# SCH_ACVoltageSensor_2025-03-02.net
KiCad netlist of a schematic drawn in EasyEDA
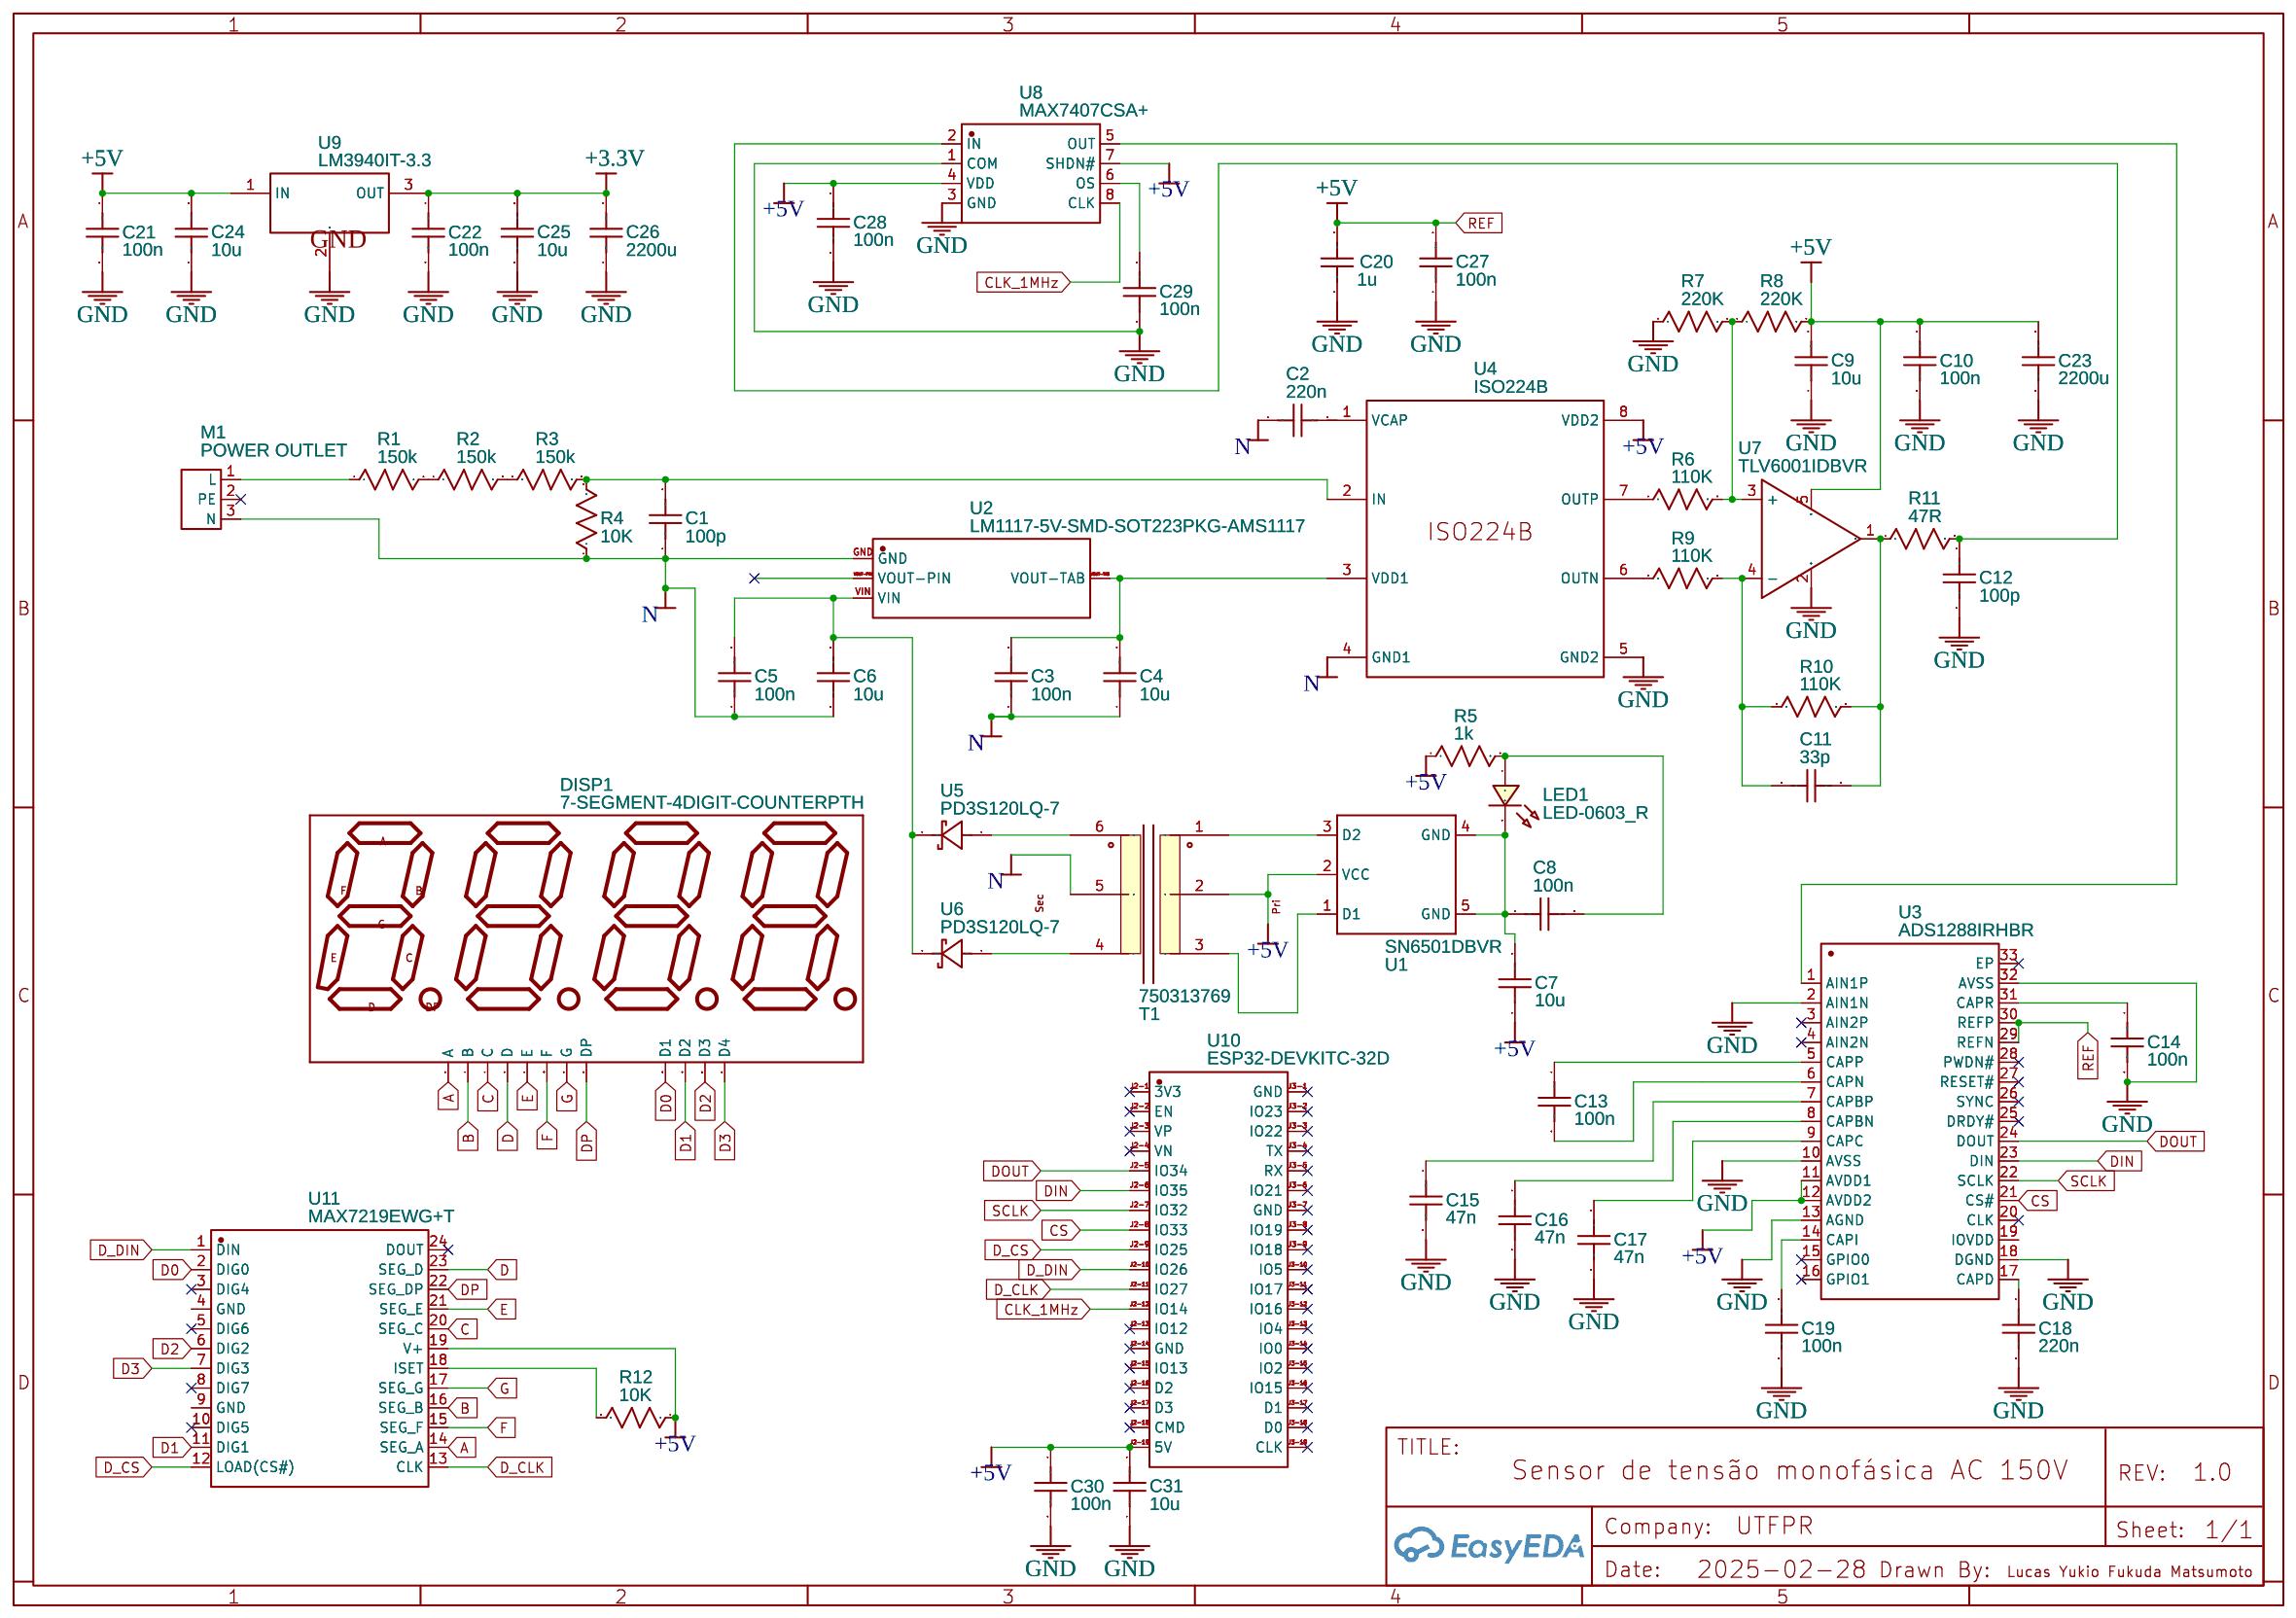
[diagram p0: schematic sheet]

(export (version "E")
  (design (tool "Eeschema 10.0.6"))
  (components
    (comp (ref "C1") (value "100p") (libsource (lib "") (part "C_0603_US_1")))
    (comp (ref "C2") (value "220n") (libsource (lib "") (part "C_0603_US_2")))
    (comp (ref "C3") (value "100n") (libsource (lib "") (part "C_0603_US_1")))
    (comp (ref "C4") (value "10u") (libsource (lib "") (part "C_0603_US_1")))
    (comp (ref "C5") (value "100n") (libsource (lib "") (part "C_0603_US_1")))
    (comp (ref "C6") (value "10u") (libsource (lib "") (part "C_0603_US_1")))
    (comp (ref "C7") (value "10u") (libsource (lib "") (part "C_0603_US_1")))
    (comp (ref "C8") (value "100n") (libsource (lib "") (part "C_0603_US_2")))
    (comp (ref "C9") (value "10u") (libsource (lib "") (part "C_0603_US_1")))
    (comp (ref "C10") (value "100n") (libsource (lib "") (part "C_0603_US")))
    (comp (ref "C11") (value "33p") (libsource (lib "") (part "C_0603_US_2")))
    (comp (ref "C12") (value "100p") (libsource (lib "") (part "C_0603_US_1")))
    (comp (ref "C13") (value "100n") (libsource (lib "") (part "C_0603_US")))
    (comp (ref "C14") (value "100n") (libsource (lib "") (part "C_0603_US")))
    (comp (ref "C15") (value "47n") (libsource (lib "") (part "C_0603_US")))
    (comp (ref "C16") (value "47n") (libsource (lib "") (part "C_0603_US")))
    (comp (ref "C17") (value "47n") (libsource (lib "") (part "C_0603_US")))
    (comp (ref "C18") (value "220n") (libsource (lib "") (part "C_0603_US")))
    (comp (ref "C19") (value "100n") (libsource (lib "") (part "C_0603_US")))
    (comp (ref "C20") (value "1u") (libsource (lib "") (part "C_0603_US_1")))
    (comp (ref "C21") (value "100n") (libsource (lib "") (part "C_0603_US")))
    (comp (ref "C22") (value "100n") (libsource (lib "") (part "C_0603_US")))
    (comp (ref "C23") (value "2200u") (libsource (lib "") (part "C_0603_US")))
    (comp (ref "C24") (value "10u") (libsource (lib "") (part "C_0603_US_1")))
    (comp (ref "C25") (value "10u") (libsource (lib "") (part "C_0603_US_1")))
    (comp (ref "C26") (value "2200u") (libsource (lib "") (part "C_0603_US_1")))
    (comp (ref "C27") (value "100n") (libsource (lib "") (part "C_0603_US_1")))
    (comp (ref "C28") (value "100n") (libsource (lib "") (part "C_0603_US")))
    (comp (ref "C29") (value "100n") (libsource (lib "") (part "C_0603_US")))
    (comp (ref "C30") (value "100n") (libsource (lib "") (part "C_0603_US")))
    (comp (ref "C31") (value "10u") (libsource (lib "") (part "C_0603_US_1")))
    (comp (ref "DISP1")
      (value "7-SEGMENT-4DIGIT-COUNTERPTH")
      (libsource (lib "") (part "7-SEGMENT-4DIGIT-COUNTERPTH"))
    )
    (comp (ref "LED1")
      (value "LED-0603_R")
      (fields
        (field (name "Manufacturer Part") "19-217/R6C-AL1M2VY/3T")
        (field (name "Manufacturer") "EVERLIGHT(台湾亿光)")
      )
      (libsource (lib "") (part "LED-0603_R"))
    )
    (comp (ref "M1") (value "POWER OUTLET") (libsource (lib "") (part "POWER OUTLET")))
    (comp (ref "R1") (value "150k") (libsource (lib "") (part "R_0603_US")))
    (comp (ref "R2") (value "150k") (libsource (lib "") (part "R_0603_US")))
    (comp (ref "R3") (value "150k") (libsource (lib "") (part "R_0603_US")))
    (comp (ref "R4") (value "10K") (libsource (lib "") (part "R_0603_US_2")))
    (comp (ref "R5") (value "1k") (libsource (lib "") (part "R_0603_US")))
    (comp (ref "R6") (value "110K") (libsource (lib "") (part "R_0603_US")))
    (comp (ref "R7") (value "220K") (libsource (lib "") (part "R_0603_US")))
    (comp (ref "R8") (value "220K") (libsource (lib "") (part "R_0603_US")))
    (comp (ref "R9") (value "110K") (libsource (lib "") (part "R_0603_US")))
    (comp (ref "R10") (value "110K") (libsource (lib "") (part "R_0603_US")))
    (comp (ref "R11") (value "47R") (libsource (lib "") (part "R_0603_US")))
    (comp (ref "R12") (value "10K") (libsource (lib "") (part "R_0603_US_1")))
    (comp (ref "T1") (value "750313769") (libsource (lib "") (part "750313769")))
    (comp (ref "U1")
      (value "SN6501DBVR")
      (fields (field (name "Manufacturer") "TI(德州仪器)"))
      (libsource (lib "") (part "SN6501DBVR"))
    )
    (comp (ref "U2")
      (value "LM1117-5V-SMD-SOT223PKG-AMS1117")
      (fields (field (name "Manufacturer Part") "AMS1117-3.3") (field (name "Manufacturer") "AMS"))
      (libsource (lib "") (part "LM1117-5V-SMD-SOT223PKG-AMS1117"))
    )
    (comp (ref "U3") (value "ADS1288IRHBR") (libsource (lib "") (part "ADS1288IRHBR")))
    (comp (ref "U4")
      (value "ISO224B")
      (fields (field (name "Manufacturer Part") "ISO224BDWVR") (field (name "Manufacturer") "TI"))
      (libsource (lib "") (part "ISO224B"))
    )
    (comp (ref "U5") (value "PD3S120LQ-7") (libsource (lib "") (part "PD3S120LQ-7")))
    (comp (ref "U6") (value "PD3S120LQ-7") (libsource (lib "") (part "PD3S120LQ-7")))
    (comp (ref "U7")
      (value "TLV6001IDBVR")
      (fields (field (name "Manufacturer") "TI"))
      (libsource (lib "") (part "TLV6001IDBVR"))
    )
    (comp (ref "U8")
      (value "MAX7407CSA+")
      (fields (field (name "Manufacturer") "ADI(亚德诺)/MAXIM(美信)"))
      (libsource (lib "") (part "MAX7407CSA+"))
    )
    (comp (ref "U9")
      (value "LM3940IT-3.3")
      (fields (field (name "Manufacturer") "TI(德州仪器)"))
      (libsource (lib "") (part "LM3940IT-3.3"))
    )
    (comp (ref "U10")
      (value "ESP32-DEVKITC-32D")
      (fields
        (field (name "Manufacturer Part") "ESP32-DevKitC-32D")
        (field (name "Manufacturer") "ESPRESSIF(乐鑫)")
      )
      (libsource (lib "") (part "ESP32-DEVKITC-32D"))
    )
    (comp (ref "U11")
      (value "MAX7219EWG+T")
      (fields (field (name "Manufacturer") "ADI(亚德诺)/MAXIM(美信)"))
      (libsource (lib "") (part "MAX7219EWG+T"))
    )
  )
  (nets
    (net (code "1") (name "+3.3V") (class "Default")
      (node (ref "C22") (pin "1") (pinfunction "1_1") (pintype "unspecified"))
      (node (ref "C25") (pin "2") (pinfunction "2_2") (pintype "unspecified"))
      (node (ref "C26") (pin "2") (pinfunction "2_2") (pintype "unspecified"))
      (node (ref "U9") (pin "3") (pinfunction "OUT_3") (pintype "passive"))
    )
    (net (code "2") (name "A") (class "Default")
      (node (ref "DISP1") (pin "11") (pinfunction "A_11") (pintype "unspecified"))
      (node (ref "U11") (pin "14") (pinfunction "SEG_A_14") (pintype "unspecified"))
    )
    (net (code "3") (name "B") (class "Default")
      (node (ref "DISP1") (pin "7") (pinfunction "B_7") (pintype "unspecified"))
      (node (ref "U11") (pin "16") (pinfunction "SEG_B_16") (pintype "unspecified"))
    )
    (net (code "4") (name "C") (class "Default")
      (node (ref "DISP1") (pin "4") (pinfunction "C_4") (pintype "unspecified"))
      (node (ref "U11") (pin "20") (pinfunction "SEG_C_20") (pintype "unspecified"))
    )
    (net (code "5") (name "CLK_1MHz") (class "Default")
      (node (ref "U10") (pin "J2-12") (pinfunction "IO14_J2-12") (pintype "unspecified"))
      (node (ref "U8") (pin "8") (pinfunction "CLK_8") (pintype "unspecified"))
    )
    (net (code "6") (name "CS") (class "Default")
      (node (ref "U10") (pin "J2-8") (pinfunction "IO33_J2-8") (pintype "unspecified"))
      (node (ref "U3") (pin "21") (pinfunction "CS#_21") (pintype "unspecified"))
    )
    (net (code "7") (name "D") (class "Default")
      (node (ref "DISP1") (pin "2") (pinfunction "D_2") (pintype "unspecified"))
      (node (ref "U11") (pin "23") (pinfunction "SEG_D_23") (pintype "unspecified"))
    )
    (net (code "8") (name "D0") (class "Default")
      (node (ref "DISP1") (pin "12") (pinfunction "D1_12") (pintype "unspecified"))
      (node (ref "U11") (pin "2") (pinfunction "DIG0_2") (pintype "unspecified"))
    )
    (net (code "9") (name "D1") (class "Default")
      (node (ref "DISP1") (pin "9") (pinfunction "D2_9") (pintype "unspecified"))
      (node (ref "U11") (pin "11") (pinfunction "DIG1_11") (pintype "unspecified"))
    )
    (net (code "10") (name "D2") (class "Default")
      (node (ref "DISP1") (pin "8") (pinfunction "D3_8") (pintype "unspecified"))
      (node (ref "U11") (pin "6") (pinfunction "DIG2_6") (pintype "unspecified"))
    )
    (net (code "11") (name "D3") (class "Default")
      (node (ref "DISP1") (pin "6") (pinfunction "D4_6") (pintype "unspecified"))
      (node (ref "U11") (pin "7") (pinfunction "DIG3_7") (pintype "unspecified"))
    )
    (net (code "12") (name "DIN") (class "Default")
      (node (ref "U10") (pin "J2-6") (pinfunction "IO35_J2-6") (pintype "unspecified"))
      (node (ref "U3") (pin "23") (pinfunction "DIN_23") (pintype "unspecified"))
    )
    (net (code "13") (name "DOUT") (class "Default")
      (node (ref "U10") (pin "J2-5") (pinfunction "IO34_J2-5") (pintype "unspecified"))
      (node (ref "U3") (pin "24") (pinfunction "DOUT_24") (pintype "unspecified"))
    )
    (net (code "14") (name "DP") (class "Default")
      (node (ref "DISP1") (pin "3") (pinfunction "DP_3") (pintype "unspecified"))
      (node (ref "U11") (pin "22") (pinfunction "SEG_DP_22") (pintype "unspecified"))
    )
    (net (code "15") (name "D_CLK") (class "Default")
      (node (ref "U10") (pin "J2-11") (pinfunction "IO27_J2-11") (pintype "unspecified"))
      (node (ref "U11") (pin "13") (pinfunction "CLK_13") (pintype "unspecified"))
    )
    (net (code "16") (name "D_CS") (class "Default")
      (node (ref "U10") (pin "J2-9") (pinfunction "IO25_J2-9") (pintype "unspecified"))
      (node (ref "U11") (pin "12") (pinfunction "LOAD(CS#)_12") (pintype "unspecified"))
    )
    (net (code "17") (name "D_DIN") (class "Default")
      (node (ref "U10") (pin "J2-10") (pinfunction "IO26_J2-10") (pintype "unspecified"))
      (node (ref "U11") (pin "1") (pinfunction "DIN_1") (pintype "unspecified"))
    )
    (net (code "18") (name "E") (class "Default")
      (node (ref "DISP1") (pin "1") (pinfunction "E_1") (pintype "unspecified"))
      (node (ref "U11") (pin "21") (pinfunction "SEG_E_21") (pintype "unspecified"))
    )
    (net (code "19") (name "F") (class "Default")
      (node (ref "DISP1") (pin "10") (pinfunction "F_10") (pintype "unspecified"))
      (node (ref "U11") (pin "15") (pinfunction "SEG_F_15") (pintype "unspecified"))
    )
    (net (code "20") (name "G") (class "Default")
      (node (ref "DISP1") (pin "5") (pinfunction "G_5") (pintype "unspecified"))
      (node (ref "U11") (pin "17") (pinfunction "SEG_G_17") (pintype "unspecified"))
    )
    (net (code "21") (name "GND") (class "Default")
      (node (ref "C10") (pin "2") (pinfunction "2_2") (pintype "unspecified"))
      (node (ref "C12") (pin "1") (pinfunction "1_1") (pintype "unspecified"))
      (node (ref "C14") (pin "2") (pinfunction "2_2") (pintype "unspecified"))
      (node (ref "C15") (pin "2") (pinfunction "2_2") (pintype "unspecified"))
      (node (ref "C16") (pin "2") (pinfunction "2_2") (pintype "unspecified"))
      (node (ref "C17") (pin "2") (pinfunction "2_2") (pintype "unspecified"))
      (node (ref "C18") (pin "2") (pinfunction "2_2") (pintype "unspecified"))
      (node (ref "C19") (pin "2") (pinfunction "2_2") (pintype "unspecified"))
      (node (ref "C20") (pin "1") (pinfunction "1_1") (pintype "unspecified"))
      (node (ref "C21") (pin "2") (pinfunction "2_2") (pintype "unspecified"))
      (node (ref "C22") (pin "2") (pinfunction "2_2") (pintype "unspecified"))
      (node (ref "C23") (pin "2") (pinfunction "2_2") (pintype "unspecified"))
      (node (ref "C24") (pin "1") (pinfunction "1_1") (pintype "unspecified"))
      (node (ref "C25") (pin "1") (pinfunction "1_1") (pintype "unspecified"))
      (node (ref "C26") (pin "1") (pinfunction "1_1") (pintype "unspecified"))
      (node (ref "C27") (pin "1") (pinfunction "1_1") (pintype "unspecified"))
      (node (ref "C28") (pin "2") (pinfunction "2_2") (pintype "unspecified"))
      (node (ref "C29") (pin "2") (pinfunction "2_2") (pintype "unspecified"))
      (node (ref "C30") (pin "2") (pinfunction "2_2") (pintype "unspecified"))
      (node (ref "C31") (pin "1") (pinfunction "1_1") (pintype "unspecified"))
      (node (ref "C9") (pin "1") (pinfunction "1_1") (pintype "unspecified"))
      (node (ref "R7") (pin "1") (pinfunction "1_1") (pintype "unspecified"))
      (node (ref "U3") (pin "10") (pinfunction "AVSS_10") (pintype "unspecified"))
      (node (ref "U3") (pin "13") (pinfunction "AGND_13") (pintype "unspecified"))
      (node (ref "U3") (pin "18") (pinfunction "DGND_18") (pintype "unspecified"))
      (node (ref "U3") (pin "2") (pinfunction "AIN1N_2") (pintype "unspecified"))
      (node (ref "U3") (pin "32") (pinfunction "AVSS_32") (pintype "unspecified"))
      (node (ref "U4") (pin "5") (pinfunction "GND2_5") (pintype "unspecified"))
      (node (ref "U7") (pin "2") (pinfunction "GND_2") (pintype "unspecified"))
      (node (ref "U8") (pin "1") (pinfunction "COM_1") (pintype "unspecified"))
      (node (ref "U8") (pin "3") (pinfunction "GND_3") (pintype "unspecified"))
      (node (ref "U9") (pin "2") (pinfunction "GND_2") (pintype "passive"))
    )
    (net (code "22") (name "N") (class "Default")
      (node (ref "C1") (pin "1") (pinfunction "1_1") (pintype "unspecified"))
      (node (ref "C2") (pin "1") (pinfunction "1_1") (pintype "unspecified"))
      (node (ref "C3") (pin "1") (pinfunction "1_1") (pintype "unspecified"))
      (node (ref "C4") (pin "1") (pinfunction "1_1") (pintype "unspecified"))
      (node (ref "C5") (pin "1") (pinfunction "1_1") (pintype "unspecified"))
      (node (ref "C6") (pin "1") (pinfunction "1_1") (pintype "unspecified"))
      (node (ref "M1") (pin "3") (pinfunction "N_3") (pintype "unspecified"))
      (node (ref "R4") (pin "1") (pinfunction "1_1") (pintype "unspecified"))
      (node (ref "T1") (pin "5") (pinfunction "5_5") (pintype "bidirectional"))
      (node (ref "U2") (pin "GND") (pinfunction "GND_GND") (pintype "unspecified"))
      (node (ref "U4") (pin "4") (pinfunction "GND1_4") (pintype "unspecified"))
    )
    (net (code "23") (name "Net-(C5-Pad2)") (class "Default")
      (node (ref "C5") (pin "2") (pinfunction "2_2") (pintype "unspecified"))
      (node (ref "C6") (pin "2") (pinfunction "2_2") (pintype "unspecified"))
      (node (ref "U2") (pin "VIN") (pinfunction "VIN_VIN") (pintype "unspecified"))
      (node (ref "U5") (pin "2") (pinfunction "2_2") (pintype "unspecified"))
      (node (ref "U6") (pin "2") (pinfunction "2_2") (pintype "unspecified"))
    )
    (net (code "24") (name "Net-(C7-Pad2)") (class "Default")
      (node (ref "C7") (pin "2") (pinfunction "2_2") (pintype "unspecified"))
      (node (ref "C8") (pin "1") (pinfunction "1_1") (pintype "unspecified"))
      (node (ref "LED1") (pin "2") (pinfunction "2_2") (pintype "unspecified"))
      (node (ref "U1") (pin "4") (pinfunction "GND_4") (pintype "unspecified"))
      (node (ref "U1") (pin "5") (pinfunction "GND_5") (pintype "unspecified"))
    )
    (net (code "25") (name "Net-(C8-Pad2)") (class "Default")
      (node (ref "C8") (pin "2") (pinfunction "2_2") (pintype "unspecified"))
      (node (ref "LED1") (pin "1") (pinfunction "1_1") (pintype "unspecified"))
      (node (ref "R5") (pin "2") (pinfunction "2_2") (pintype "unspecified"))
    )
    (net (code "26") (name "Net-(M1-L)") (class "Default")
      (node (ref "M1") (pin "1") (pinfunction "L_1") (pintype "unspecified"))
      (node (ref "R1") (pin "1") (pinfunction "1_1") (pintype "unspecified"))
    )
    (net (code "27") (name "Net-(R1-Pad2)") (class "Default")
      (node (ref "R1") (pin "2") (pinfunction "2_2") (pintype "unspecified"))
      (node (ref "R2") (pin "1") (pinfunction "1_1") (pintype "unspecified"))
    )
    (net (code "28") (name "Net-(R2-Pad2)") (class "Default")
      (node (ref "R2") (pin "2") (pinfunction "2_2") (pintype "unspecified"))
      (node (ref "R3") (pin "1") (pinfunction "1_1") (pintype "unspecified"))
    )
    (net (code "29") (name "Net-(T1-Pad4)") (class "Default")
      (node (ref "T1") (pin "4") (pinfunction "4_4") (pintype "bidirectional"))
      (node (ref "U6") (pin "1") (pinfunction "1_1") (pintype "unspecified"))
    )
    (net (code "30") (name "Net-(T1-Pad6)") (class "Default")
      (node (ref "T1") (pin "6") (pinfunction "6_6") (pintype "bidirectional"))
      (node (ref "U5") (pin "1") (pinfunction "1_1") (pintype "unspecified"))
    )
    (net (code "31") (name "Net-(U1-D1)") (class "Default")
      (node (ref "T1") (pin "3") (pinfunction "3_3") (pintype "bidirectional"))
      (node (ref "U1") (pin "1") (pinfunction "D1_1") (pintype "unspecified"))
    )
    (net (code "32") (name "Net-(U1-D2)") (class "Default")
      (node (ref "T1") (pin "1") (pinfunction "1_1") (pintype "bidirectional"))
      (node (ref "U1") (pin "3") (pinfunction "D2_3") (pintype "unspecified"))
    )
    (net (code "33") (name "Net-(U3-AIN1P)") (class "Default")
      (node (ref "U3") (pin "1") (pinfunction "AIN1P_1") (pintype "unspecified"))
      (node (ref "U8") (pin "5") (pinfunction "OUT_5") (pintype "unspecified"))
    )
    (net (code "34") (name "Net-(U3-CAPBN)") (class "Default")
      (node (ref "C16") (pin "1") (pinfunction "1_1") (pintype "unspecified"))
      (node (ref "U3") (pin "8") (pinfunction "CAPBN_8") (pintype "unspecified"))
    )
    (net (code "35") (name "Net-(U3-CAPBP)") (class "Default")
      (node (ref "C15") (pin "1") (pinfunction "1_1") (pintype "unspecified"))
      (node (ref "U3") (pin "7") (pinfunction "CAPBP_7") (pintype "unspecified"))
    )
    (net (code "36") (name "Net-(U3-CAPC)") (class "Default")
      (node (ref "C17") (pin "1") (pinfunction "1_1") (pintype "unspecified"))
      (node (ref "U3") (pin "9") (pinfunction "CAPC_9") (pintype "unspecified"))
    )
    (net (code "37") (name "Net-(U3-CAPD)") (class "Default")
      (node (ref "C18") (pin "1") (pinfunction "1_1") (pintype "unspecified"))
      (node (ref "U3") (pin "17") (pinfunction "CAPD_17") (pintype "unspecified"))
    )
    (net (code "38") (name "Net-(U3-CAPI)") (class "Default")
      (node (ref "C19") (pin "1") (pinfunction "1_1") (pintype "unspecified"))
      (node (ref "U3") (pin "14") (pinfunction "CAPI_14") (pintype "unspecified"))
    )
    (net (code "39") (name "Net-(U3-CAPN)") (class "Default")
      (node (ref "C13") (pin "2") (pinfunction "2_2") (pintype "unspecified"))
      (node (ref "U3") (pin "6") (pinfunction "CAPN_6") (pintype "unspecified"))
    )
    (net (code "40") (name "Net-(U3-CAPP)") (class "Default")
      (node (ref "C13") (pin "1") (pinfunction "1_1") (pintype "unspecified"))
      (node (ref "U3") (pin "5") (pinfunction "CAPP_5") (pintype "unspecified"))
    )
    (net (code "41") (name "Net-(U3-CAPR)") (class "Default")
      (node (ref "C14") (pin "1") (pinfunction "1_1") (pintype "unspecified"))
      (node (ref "U3") (pin "31") (pinfunction "CAPR_31") (pintype "unspecified"))
    )
    (net (code "42") (name "Net-(U4-IN)") (class "Default")
      (node (ref "C1") (pin "2") (pinfunction "2_2") (pintype "unspecified"))
      (node (ref "R3") (pin "2") (pinfunction "2_2") (pintype "unspecified"))
      (node (ref "R4") (pin "2") (pinfunction "2_2") (pintype "unspecified"))
      (node (ref "U4") (pin "2") (pinfunction "IN_2") (pintype "unspecified"))
    )
    (net (code "43") (name "Net-(U4-OUTN)") (class "Default")
      (node (ref "R9") (pin "1") (pinfunction "1_1") (pintype "unspecified"))
      (node (ref "U4") (pin "6") (pinfunction "OUTN_6") (pintype "unspecified"))
    )
    (net (code "44") (name "Net-(U4-OUTP)") (class "Default")
      (node (ref "R6") (pin "1") (pinfunction "1_1") (pintype "unspecified"))
      (node (ref "U4") (pin "7") (pinfunction "OUTP_7") (pintype "unspecified"))
    )
    (net (code "45") (name "Net-(U4-VDD1)") (class "Default")
      (node (ref "C3") (pin "2") (pinfunction "2_2") (pintype "unspecified"))
      (node (ref "C4") (pin "2") (pinfunction "2_2") (pintype "unspecified"))
      (node (ref "U2") (pin "VOUT-TAB") (pinfunction "VOUT-TAB_VOUT-TAB") (pintype "unspecified"))
      (node (ref "U4") (pin "3") (pinfunction "VDD1_3") (pintype "unspecified"))
    )
    (net (code "46") (name "Net-(U7-+)") (class "Default")
      (node (ref "R6") (pin "2") (pinfunction "2_2") (pintype "unspecified"))
      (node (ref "R7") (pin "2") (pinfunction "2_2") (pintype "unspecified"))
      (node (ref "R8") (pin "1") (pinfunction "1_1") (pintype "unspecified"))
      (node (ref "U7") (pin "3") (pinfunction "+_3") (pintype "unspecified"))
    )
    (net (code "47") (name "Net-(U7--)") (class "Default")
      (node (ref "C11") (pin "1") (pinfunction "1_1") (pintype "unspecified"))
      (node (ref "R10") (pin "1") (pinfunction "1_1") (pintype "unspecified"))
      (node (ref "R9") (pin "2") (pinfunction "2_2") (pintype "unspecified"))
      (node (ref "U7") (pin "4") (pinfunction "-_4") (pintype "unspecified"))
    )
    (net (code "48") (name "Net-(U7-OUT)") (class "Default")
      (node (ref "C11") (pin "2") (pinfunction "2_2") (pintype "unspecified"))
      (node (ref "R10") (pin "2") (pinfunction "2_2") (pintype "unspecified"))
      (node (ref "R11") (pin "1") (pinfunction "1_1") (pintype "unspecified"))
      (node (ref "U7") (pin "1") (pinfunction "OUT_1") (pintype "unspecified"))
    )
    (net (code "49") (name "Net-(U8-IN)") (class "Default")
      (node (ref "C12") (pin "2") (pinfunction "2_2") (pintype "unspecified"))
      (node (ref "R11") (pin "2") (pinfunction "2_2") (pintype "unspecified"))
      (node (ref "U8") (pin "2") (pinfunction "IN_2") (pintype "unspecified"))
    )
    (net (code "50") (name "Net-(U8-OS)") (class "Default")
      (node (ref "C29") (pin "1") (pinfunction "1_1") (pintype "unspecified"))
      (node (ref "U8") (pin "6") (pinfunction "OS_6") (pintype "unspecified"))
    )
    (net (code "51") (name "Net-(U11-ISET)") (class "Default")
      (node (ref "R12") (pin "2") (pinfunction "2_2") (pintype "unspecified"))
      (node (ref "U11") (pin "18") (pinfunction "ISET_18") (pintype "unspecified"))
    )
    (net (code "52") (name "REF") (class "Default")
      (node (ref "C10") (pin "1") (pinfunction "1_1") (pintype "unspecified"))
      (node (ref "C20") (pin "2") (pinfunction "2_2") (pintype "unspecified"))
      (node (ref "C21") (pin "1") (pinfunction "1_1") (pintype "unspecified"))
      (node (ref "C23") (pin "1") (pinfunction "1_1") (pintype "unspecified"))
      (node (ref "C24") (pin "2") (pinfunction "2_2") (pintype "unspecified"))
      (node (ref "C27") (pin "2") (pinfunction "2_2") (pintype "unspecified"))
      (node (ref "C28") (pin "1") (pinfunction "1_1") (pintype "unspecified"))
      (node (ref "C30") (pin "1") (pinfunction "1_1") (pintype "unspecified"))
      (node (ref "C31") (pin "2") (pinfunction "2_2") (pintype "unspecified"))
      (node (ref "C7") (pin "1") (pinfunction "1_1") (pintype "unspecified"))
      (node (ref "C9") (pin "2") (pinfunction "2_2") (pintype "unspecified"))
      (node (ref "R12") (pin "1") (pinfunction "1_1") (pintype "unspecified"))
      (node (ref "R5") (pin "1") (pinfunction "1_1") (pintype "unspecified"))
      (node (ref "R8") (pin "2") (pinfunction "2_2") (pintype "unspecified"))
      (node (ref "T1") (pin "2") (pinfunction "2_2") (pintype "bidirectional"))
      (node (ref "U1") (pin "2") (pinfunction "VCC_2") (pintype "unspecified"))
      (node (ref "U10") (pin "J2-19") (pinfunction "5V_J2-19") (pintype "unspecified"))
      (node (ref "U11") (pin "19") (pinfunction "V+_19") (pintype "unspecified"))
      (node (ref "U3") (pin "11") (pinfunction "AVDD1_11") (pintype "unspecified"))
      (node (ref "U3") (pin "12") (pinfunction "AVDD2_12") (pintype "unspecified"))
      (node (ref "U3") (pin "29") (pinfunction "REFN_29") (pintype "unspecified"))
      (node (ref "U3") (pin "30") (pinfunction "REFP_30") (pintype "unspecified"))
      (node (ref "U4") (pin "8") (pinfunction "VDD2_8") (pintype "unspecified"))
      (node (ref "U7") (pin "5") (pinfunction "VDD_5") (pintype "unspecified"))
      (node (ref "U8") (pin "4") (pinfunction "VDD_4") (pintype "unspecified"))
      (node (ref "U8") (pin "7") (pinfunction "SHDN#_7") (pintype "unspecified"))
      (node (ref "U9") (pin "1") (pinfunction "IN_1") (pintype "passive"))
    )
    (net (code "53") (name "SCLK") (class "Default")
      (node (ref "U10") (pin "J2-7") (pinfunction "IO32_J2-7") (pintype "unspecified"))
      (node (ref "U3") (pin "22") (pinfunction "SCLK_22") (pintype "unspecified"))
    )
    (net (code "54") (name "unconnected-(C2-Pad2)") (class "Default")
      (node (ref "C2") (pin "2") (pinfunction "2_2") (pintype "unspecified"))
    )
    (net (code "55") (name "unconnected-(M1-PE-Pad2)") (class "Default")
      (node (ref "M1") (pin "2") (pinfunction "PE_2") (pintype "unspecified+no_connect"))
    )
    (net (code "56") (name "unconnected-(U2-PadVOUT-PIN)") (class "Default")
      (node (ref "U2") (pin "VOUT-PIN") (pinfunction "VOUT-PIN_VOUT-PIN") (pintype "unspecified+no_connect"))
    )
    (net (code "57") (name "unconnected-(U3-AIN2N-Pad4)") (class "Default")
      (node (ref "U3") (pin "4") (pinfunction "AIN2N_4") (pintype "unspecified+no_connect"))
    )
    (net (code "58") (name "unconnected-(U3-AIN2P-Pad3)") (class "Default")
      (node (ref "U3") (pin "3") (pinfunction "AIN2P_3") (pintype "unspecified+no_connect"))
    )
    (net (code "59") (name "unconnected-(U3-CLK-Pad20)") (class "Default")
      (node (ref "U3") (pin "20") (pinfunction "CLK_20") (pintype "unspecified+no_connect"))
    )
    (net (code "60") (name "unconnected-(U3-DRDY#-Pad25)") (class "Default")
      (node (ref "U3") (pin "25") (pinfunction "DRDY#_25") (pintype "unspecified+no_connect"))
    )
    (net (code "61") (name "unconnected-(U3-EP-Pad33)") (class "Default")
      (node (ref "U3") (pin "33") (pinfunction "EP_33") (pintype "unspecified+no_connect"))
    )
    (net (code "62") (name "unconnected-(U3-GPIO0-Pad15)") (class "Default")
      (node (ref "U3") (pin "15") (pinfunction "GPIO0_15") (pintype "unspecified+no_connect"))
    )
    (net (code "63") (name "unconnected-(U3-GPIO1-Pad16)") (class "Default")
      (node (ref "U3") (pin "16") (pinfunction "GPIO1_16") (pintype "unspecified+no_connect"))
    )
    (net (code "64") (name "unconnected-(U3-IOVDD-Pad19)") (class "Default")
      (node (ref "U3") (pin "19") (pinfunction "IOVDD_19") (pintype "unspecified"))
    )
    (net (code "65") (name "unconnected-(U3-PWDN#-Pad28)") (class "Default")
      (node (ref "U3") (pin "28") (pinfunction "PWDN#_28") (pintype "unspecified+no_connect"))
    )
    (net (code "66") (name "unconnected-(U3-RESET#-Pad27)") (class "Default")
      (node (ref "U3") (pin "27") (pinfunction "RESET#_27") (pintype "unspecified+no_connect"))
    )
    (net (code "67") (name "unconnected-(U3-SYNC-Pad26)") (class "Default")
      (node (ref "U3") (pin "26") (pinfunction "SYNC_26") (pintype "unspecified+no_connect"))
    )
    (net (code "68") (name "unconnected-(U4-VCAP-Pad1)") (class "Default")
      (node (ref "U4") (pin "1") (pinfunction "VCAP_1") (pintype "unspecified"))
    )
    (net (code "69") (name "unconnected-(U10-3V3-PadJ2-1)") (class "Default")
      (node (ref "U10") (pin "J2-1") (pinfunction "3V3_J2-1") (pintype "unspecified+no_connect"))
    )
    (net (code "70") (name "unconnected-(U10-CLK-PadJ3-19)") (class "Default")
      (node (ref "U10") (pin "J3-19") (pinfunction "CLK_J3-19") (pintype "unspecified+no_connect"))
    )
    (net (code "71") (name "unconnected-(U10-CMD-PadJ2-18)") (class "Default")
      (node (ref "U10") (pin "J2-18") (pinfunction "CMD_J2-18") (pintype "unspecified+no_connect"))
    )
    (net (code "72") (name "unconnected-(U10-D0-PadJ3-18)") (class "Default")
      (node (ref "U10") (pin "J3-18") (pinfunction "D0_J3-18") (pintype "unspecified+no_connect"))
    )
    (net (code "73") (name "unconnected-(U10-D1-PadJ3-17)") (class "Default")
      (node (ref "U10") (pin "J3-17") (pinfunction "D1_J3-17") (pintype "unspecified+no_connect"))
    )
    (net (code "74") (name "unconnected-(U10-D2-PadJ2-16)") (class "Default")
      (node (ref "U10") (pin "J2-16") (pinfunction "D2_J2-16") (pintype "unspecified+no_connect"))
    )
    (net (code "75") (name "unconnected-(U10-D3-PadJ2-17)") (class "Default")
      (node (ref "U10") (pin "J2-17") (pinfunction "D3_J2-17") (pintype "unspecified+no_connect"))
    )
    (net (code "76") (name "unconnected-(U10-EN-PadJ2-2)") (class "Default")
      (node (ref "U10") (pin "J2-2") (pinfunction "EN_J2-2") (pintype "unspecified+no_connect"))
    )
    (net (code "77") (name "unconnected-(U10-GND-PadJ2-14)") (class "Default")
      (node (ref "U10") (pin "J2-14") (pinfunction "GND_J2-14") (pintype "unspecified+no_connect"))
    )
    (net (code "78") (name "unconnected-(U10-GND-PadJ3-1)") (class "Default")
      (node (ref "U10") (pin "J3-1") (pinfunction "GND_J3-1") (pintype "unspecified+no_connect"))
    )
    (net (code "79") (name "unconnected-(U10-GND-PadJ3-7)") (class "Default")
      (node (ref "U10") (pin "J3-7") (pinfunction "GND_J3-7") (pintype "unspecified+no_connect"))
    )
    (net (code "80") (name "unconnected-(U10-IO0-PadJ3-14)") (class "Default")
      (node (ref "U10") (pin "J3-14") (pinfunction "IO0_J3-14") (pintype "unspecified+no_connect"))
    )
    (net (code "81") (name "unconnected-(U10-IO2-PadJ3-15)") (class "Default")
      (node (ref "U10") (pin "J3-15") (pinfunction "IO2_J3-15") (pintype "unspecified+no_connect"))
    )
    (net (code "82") (name "unconnected-(U10-IO4-PadJ3-13)") (class "Default")
      (node (ref "U10") (pin "J3-13") (pinfunction "IO4_J3-13") (pintype "unspecified+no_connect"))
    )
    (net (code "83") (name "unconnected-(U10-IO5-PadJ3-10)") (class "Default")
      (node (ref "U10") (pin "J3-10") (pinfunction "IO5_J3-10") (pintype "unspecified+no_connect"))
    )
    (net (code "84") (name "unconnected-(U10-IO12-PadJ2-13)") (class "Default")
      (node (ref "U10") (pin "J2-13") (pinfunction "IO12_J2-13") (pintype "unspecified+no_connect"))
    )
    (net (code "85") (name "unconnected-(U10-IO13-PadJ2-15)") (class "Default")
      (node (ref "U10") (pin "J2-15") (pinfunction "IO13_J2-15") (pintype "unspecified+no_connect"))
    )
    (net (code "86") (name "unconnected-(U10-IO15-PadJ3-16)") (class "Default")
      (node (ref "U10") (pin "J3-16") (pinfunction "IO15_J3-16") (pintype "unspecified+no_connect"))
    )
    (net (code "87") (name "unconnected-(U10-IO16-PadJ3-12)") (class "Default")
      (node (ref "U10") (pin "J3-12") (pinfunction "IO16_J3-12") (pintype "unspecified+no_connect"))
    )
    (net (code "88") (name "unconnected-(U10-IO17-PadJ3-11)") (class "Default")
      (node (ref "U10") (pin "J3-11") (pinfunction "IO17_J3-11") (pintype "unspecified+no_connect"))
    )
    (net (code "89") (name "unconnected-(U10-IO18-PadJ3-9)") (class "Default")
      (node (ref "U10") (pin "J3-9") (pinfunction "IO18_J3-9") (pintype "unspecified+no_connect"))
    )
    (net (code "90") (name "unconnected-(U10-IO19-PadJ3-8)") (class "Default")
      (node (ref "U10") (pin "J3-8") (pinfunction "IO19_J3-8") (pintype "unspecified+no_connect"))
    )
    (net (code "91") (name "unconnected-(U10-IO21-PadJ3-6)") (class "Default")
      (node (ref "U10") (pin "J3-6") (pinfunction "IO21_J3-6") (pintype "unspecified+no_connect"))
    )
    (net (code "92") (name "unconnected-(U10-IO22-PadJ3-3)") (class "Default")
      (node (ref "U10") (pin "J3-3") (pinfunction "IO22_J3-3") (pintype "unspecified+no_connect"))
    )
    (net (code "93") (name "unconnected-(U10-IO23-PadJ3-2)") (class "Default")
      (node (ref "U10") (pin "J3-2") (pinfunction "IO23_J3-2") (pintype "unspecified+no_connect"))
    )
    (net (code "94") (name "unconnected-(U10-RX-PadJ3-5)") (class "Default")
      (node (ref "U10") (pin "J3-5") (pinfunction "RX_J3-5") (pintype "unspecified+no_connect"))
    )
    (net (code "95") (name "unconnected-(U10-TX-PadJ3-4)") (class "Default")
      (node (ref "U10") (pin "J3-4") (pinfunction "TX_J3-4") (pintype "unspecified+no_connect"))
    )
    (net (code "96") (name "unconnected-(U10-VN-PadJ2-4)") (class "Default")
      (node (ref "U10") (pin "J2-4") (pinfunction "VN_J2-4") (pintype "unspecified+no_connect"))
    )
    (net (code "97") (name "unconnected-(U10-VP-PadJ2-3)") (class "Default")
      (node (ref "U10") (pin "J2-3") (pinfunction "VP_J2-3") (pintype "unspecified+no_connect"))
    )
    (net (code "98") (name "unconnected-(U11-DIG4-Pad3)") (class "Default")
      (node (ref "U11") (pin "3") (pinfunction "DIG4_3") (pintype "unspecified+no_connect"))
    )
    (net (code "99") (name "unconnected-(U11-DIG5-Pad10)") (class "Default")
      (node (ref "U11") (pin "10") (pinfunction "DIG5_10") (pintype "unspecified+no_connect"))
    )
    (net (code "100") (name "unconnected-(U11-DIG6-Pad5)") (class "Default")
      (node (ref "U11") (pin "5") (pinfunction "DIG6_5") (pintype "unspecified+no_connect"))
    )
    (net (code "101") (name "unconnected-(U11-DIG7-Pad8)") (class "Default")
      (node (ref "U11") (pin "8") (pinfunction "DIG7_8") (pintype "unspecified+no_connect"))
    )
    (net (code "102") (name "unconnected-(U11-DOUT-Pad24)") (class "Default")
      (node (ref "U11") (pin "24") (pinfunction "DOUT_24") (pintype "unspecified+no_connect"))
    )
    (net (code "103") (name "unconnected-(U11-GND-Pad4)") (class "Default")
      (node (ref "U11") (pin "4") (pinfunction "GND_4") (pintype "unspecified"))
    )
    (net (code "104") (name "unconnected-(U11-GND-Pad9)") (class "Default")
      (node (ref "U11") (pin "9") (pinfunction "GND_9") (pintype "unspecified"))
    )
  )
)
